# power_12V.net
KiCad netlist of a schematic drawn in Altium Designer
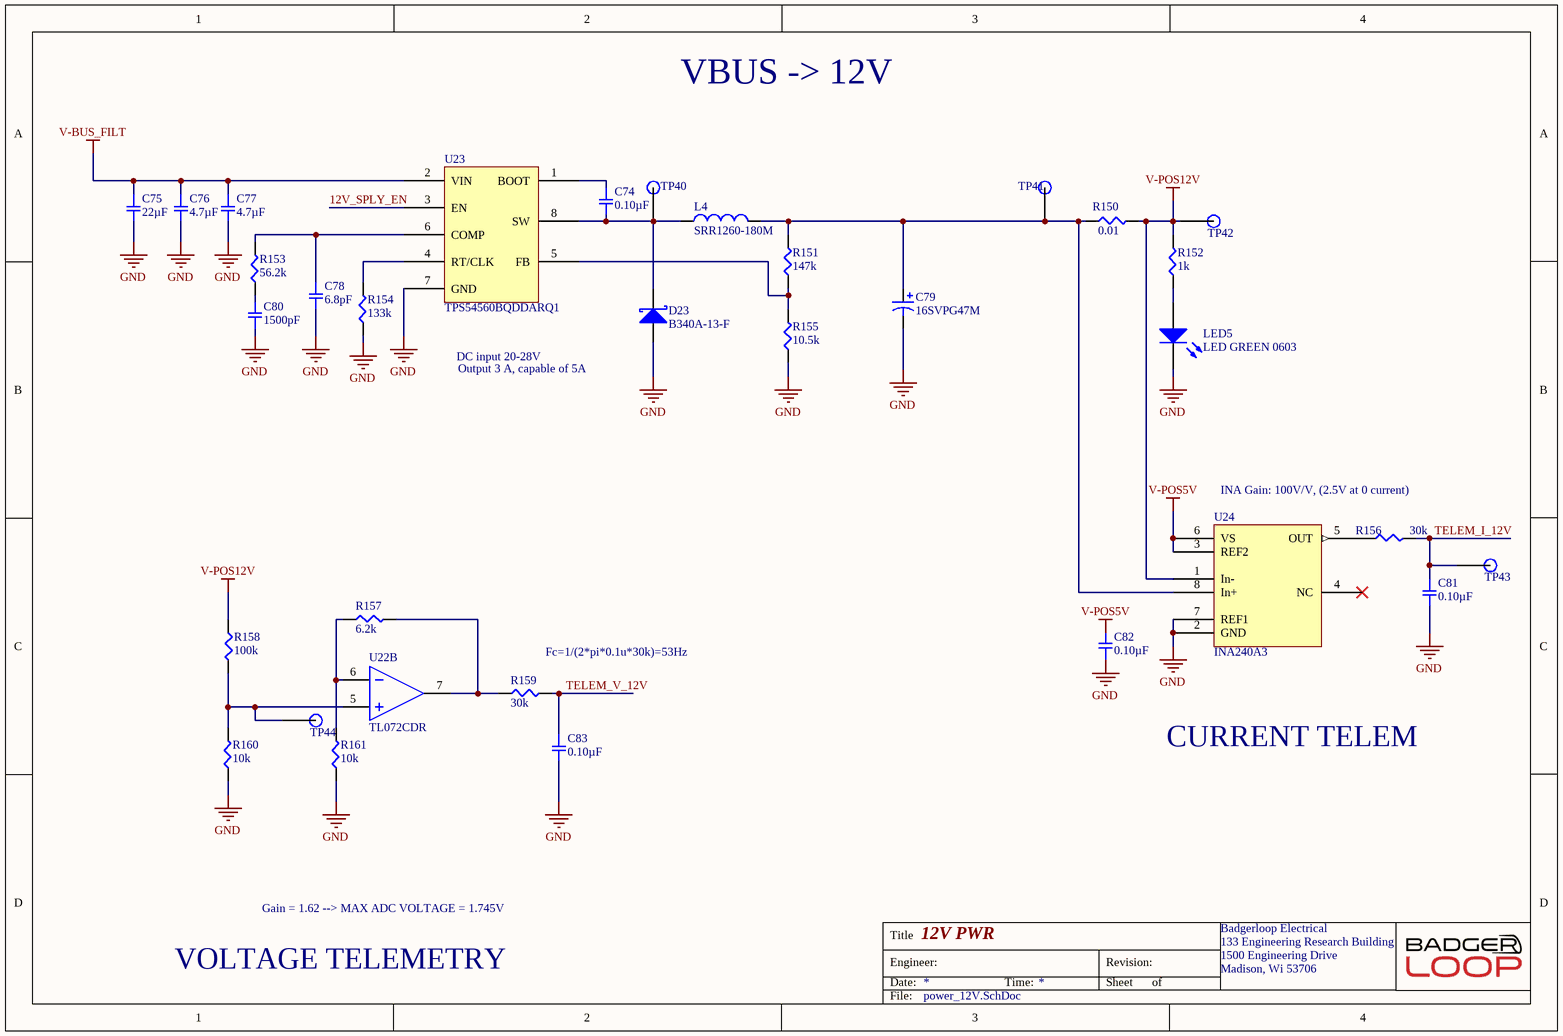
[diagram p0: power_12V.SchDoc]

(export (version "E")
  (design (tool "Eeschema 10.0.6"))
  (components
    (comp (ref "C74")
      (value "0.10µF")
      (footprint "SMD-1206C")
      (description "CAP CER 0.1UF 50V NP0 1206")
      (fields
        (field (name "DIGI-KEY PART NUMBER") "490-8335-1-ND")
        (field (name "PART NUMBER") "GRM31C5C1H104JA01K")
      )
      (libsource (lib "capacitors") (part "GRM31C5C1H104JA01K"))
    )
    (comp (ref "C75")
      (value "22µF")
      (footprint "SMD-1206C")
      (description "CAP CER 22UF 25V X5R 1206")
      (fields
        (field (name "DIGI-KEY PART NUMBER") "490-12451-1-ND")
        (field (name "PART NUMBER") "GRT31CR61E226ME01L")
      )
      (libsource (lib "capacitors") (part "GRT31CR61E226ME01L"))
    )
    (comp (ref "C76")
      (value "4.7µF")
      (footprint "SMD-1206C")
      (description "CAP CER 4.7UF 50V X7S 1206")
      (fields
        (field (name "DIGI-KEY PART NUMBER") "490-11167-1-ND")
        (field (name "PART NUMBER") "GCM31CC71H475KA03L")
      )
      (libsource (lib "capacitors") (part "GCM31CC71H475KA03L"))
    )
    (comp (ref "C77")
      (value "4.7µF")
      (footprint "SMD-1206C")
      (description "CAP CER 4.7UF 50V X7S 1206")
      (fields
        (field (name "DIGI-KEY PART NUMBER") "490-11167-1-ND")
        (field (name "PART NUMBER") "GCM31CC71H475KA03L")
      )
      (libsource (lib "capacitors") (part "GCM31CC71H475KA03L"))
    )
    (comp (ref "C78")
      (value "6.8pF")
      (footprint "SMD-0805C")
      (description "CAP CER 6.8PF 100V NP0 0805")
      (fields
        (field (name "DIGI-KEY PART NUMBER") "490-3596-1-ND")
        (field (name "PART NUMBER") "GQM2195C2A6R8CB01D")
      )
      (libsource (lib "capacitors") (part "GQM2195C2A6R8CB01D"))
    )
    (comp (ref "C79")
      (value "16SVPG47M")
      (footprint "CAPAE110103X126M")
      (fields (field (name "MANUFACTURER") "Panasonic") (field (name "TOLERANCE") "20%"))
      (libsource (lib "capacitors") (part "16SVPG47M"))
    )
    (comp (ref "C80")
      (value "1500pF")
      (footprint "SMD-0805C")
      (description "CAP CER 1500PF 50V NP0 0805")
      (fields
        (field (name "DIGI-KEY PART NUMBER") "490-7772-1-ND")
        (field (name "PART NUMBER") "GRM2165C1H152FA01D")
      )
      (libsource (lib "capacitors") (part "GRM2165C1H152FA01D"))
    )
    (comp (ref "C81")
      (value "0.10µF")
      (footprint "SMD-0805C")
      (description "CAP CER 0.1UF 16V X7R 0805")
      (fields
        (field (name "DIGI-KEY PART NUMBER") "490-1683-1-ND")
        (field (name "PART NUMBER") "GRM219R71C104KA01D")
      )
      (libsource (lib "capacitors") (part "GRM219R71C104KA01D"))
    )
    (comp (ref "C82")
      (value "0.10µF")
      (footprint "SMD-0805C")
      (description "CAP CER 0.1UF 10V U2J 0805")
      (fields
        (field (name "DIGI-KEY PART NUMBER") "490-11592-1-ND")
        (field (name "PART NUMBER") "GRM21B7U1A104JA01L")
      )
      (libsource (lib "capacitors") (part "GRM21B7U1A104JA01L"))
    )
    (comp (ref "C83")
      (value "0.10µF")
      (footprint "SMD-0805C")
      (description "CAP CER 0.1UF 16V X7R 0805")
      (fields
        (field (name "DIGI-KEY PART NUMBER") "490-1683-1-ND")
        (field (name "PART NUMBER") "GRM219R71C104KA01D")
      )
      (libsource (lib "capacitors") (part "GRM219R71C104KA01D"))
    )
    (comp (ref "D23")
      (value "B340A-13-F")
      (footprint "DIOM4326X20N")
      (description "DIODE SCHOTTKY 40V 3A SMA")
      (fields (field (name "MANUFACTURER") "Diodes") (field (name "VOLTAGE") "40V"))
      (libsource (lib "misc") (part "B340A-13-F"))
    )
    (comp (ref "L4")
      (value "SRR1260-180M")
      (footprint "INDM125125X60N")
      (fields (field (name "MANUFACTURER") "Bourns") (field (name "TOLERANCE") "20%"))
      (libsource (lib "inductor") (part "SRR1260-180M"))
    )
    (comp (ref "LED5")
      (value "LED GREEN 0603")
      (footprint "LED 0603 GREEN")
      (fields (field (name "MANUFACTURER") "Lite-On Inc."))
      (libsource (lib "misc") (part "LED GREEN 0603"))
    )
    (comp (ref "R150")
      (value "0.01")
      (footprint "SMD-1206-RES")
      (description "RES SMD 0.01 OHM 1% 1/2W 1206")
      (fields
        (field (name "PART NUMBER") "ERJ-MP2KF10MU")
        (field (name "DIGI-KEY PART NUMBER") "P19322CT-ND")
      )
      (libsource (lib "resistors") (part "ERJ-MP2KF10MU"))
    )
    (comp (ref "R151")
      (value "147k")
      (footprint "SMD-0805-RES")
      (description "RES SMD 147K OHM 1% 1/8W 0805")
      (fields
        (field (name "PART NUMBER") "ERJ-6ENF1473V")
        (field (name "DIGI-KEY PART NUMBER") "P147KCCT-ND")
      )
      (libsource (lib "resistors") (part "ERJ-6ENF1473V"))
    )
    (comp (ref "R152")
      (value "1k")
      (footprint "SMD-0805-RES")
      (description "RES SMD 1K OHM 5% 1/2W 0805")
      (fields
        (field (name "PART NUMBER") "ERJ-P06J102V")
        (field (name "DIGI-KEY PART NUMBER") "P1.0KADCT-ND")
      )
      (libsource (lib "resistors") (part "ERJ-P06J102V"))
    )
    (comp (ref "R153")
      (value "56.2k")
      (footprint "SMD-1206-RES")
      (description "RES SMD 56.2K OHM 1% 1/4W 1206")
      (fields
        (field (name "PART NUMBER") "ERJ-8ENF5622V")
        (field (name "DIGI-KEY PART NUMBER") "P56.2KFCT-ND")
      )
      (libsource (lib "resistors") (part "ERJ-8ENF5622V"))
    )
    (comp (ref "R154")
      (value "133k")
      (footprint "SMD-1206-RES")
      (description "RES SMD 133K OHM 1% 1/4W 1206")
      (fields
        (field (name "PART NUMBER") "ERJ-8ENF1333V")
        (field (name "DIGI-KEY PART NUMBER") "P133KFCT-ND")
      )
      (libsource (lib "resistors") (part "ERJ-8ENF1333V"))
    )
    (comp (ref "R155")
      (value "10.5k")
      (footprint "SMD-1206-RES")
      (description "RES SMD 10.5K OHM 1% 1/4W 1206")
      (fields
        (field (name "PART NUMBER") "ERJ-8ENF1052V")
        (field (name "DIGI-KEY PART NUMBER") "P10.5KFCT-ND")
      )
      (libsource (lib "resistors") (part "ERJ-8ENF1052V"))
    )
    (comp (ref "R156")
      (value "30k")
      (footprint "SMD-0805-RES")
      (description "RES SMD 30K OHM 1% 1/8W 0805")
      (fields
        (field (name "PART NUMBER") "ERJ-6ENF3002V")
        (field (name "DIGI-KEY PART NUMBER") "P30.0KCCT-ND")
      )
      (libsource (lib "resistors") (part "ERJ-6ENF3002V"))
    )
    (comp (ref "R157")
      (value "6.2k")
      (footprint "SMD-0805-RES")
      (description "RES SMD 6.2K OHM 5% 1/2W 0805")
      (fields
        (field (name "PART NUMBER") "ERJ-P06J622V")
        (field (name "DIGI-KEY PART NUMBER") "P6.2KADCT-ND")
      )
      (libsource (lib "resistors") (part "ERJ-P06J622V"))
    )
    (comp (ref "R158")
      (value "100k")
      (footprint "SMD-0805-RES")
      (description "RES SMD 100K OHM 5% 1/2W 0805")
      (fields
        (field (name "PART NUMBER") "ERJ-P06J104V")
        (field (name "DIGI-KEY PART NUMBER") "P100KADCT-ND")
      )
      (libsource (lib "resistors") (part "ERJ-P06J104V"))
    )
    (comp (ref "R159")
      (value "30k")
      (footprint "SMD-0805-RES")
      (description "RES SMD 30K OHM 5% 1/2W 0805")
      (fields (field (name "PART NUMBER") "ERJ-P06J303V") (field (name "DIGI-KEY PART NUMBER") "P30KADCT-ND"))
      (libsource (lib "resistors") (part "ERJ-P06J303V"))
    )
    (comp (ref "R160")
      (value "10k")
      (footprint "SMD-0805-RES")
      (description "RES SMD 10K OHM 5% 1/2W 0805")
      (fields (field (name "PART NUMBER") "ERJ-P06J103V") (field (name "DIGI-KEY PART NUMBER") "P10KADCT-ND"))
      (libsource (lib "resistors") (part "ERJ-P06J103V"))
    )
    (comp (ref "R161")
      (value "10k")
      (footprint "SMD-0805-RES")
      (description "RES SMD 10K OHM 5% 1/2W 0805")
      (fields (field (name "PART NUMBER") "ERJ-P06J103V") (field (name "DIGI-KEY PART NUMBER") "P10KADCT-ND"))
      (libsource (lib "resistors") (part "ERJ-P06J103V"))
    )
    (comp (ref "TP40")
      (value "TP")
      (footprint "Test Point")
      (description "SMD TEST POINT")
      (libsource (lib "misc") (part "TP"))
    )
    (comp (ref "TP41")
      (value "TP")
      (footprint "Test Point")
      (description "SMD TEST POINT")
      (libsource (lib "misc") (part "TP"))
    )
    (comp (ref "TP42")
      (value "TP")
      (footprint "Test Point")
      (description "SMD TEST POINT")
      (libsource (lib "misc") (part "TP"))
    )
    (comp (ref "TP43")
      (value "TP")
      (footprint "Test Point")
      (description "SMD TEST POINT")
      (libsource (lib "misc") (part "TP"))
    )
    (comp (ref "TP44")
      (value "TP")
      (footprint "Test Point")
      (description "SMD TEST POINT")
      (libsource (lib "misc") (part "TP"))
    )
    (comp (ref "U22")
      (value "TL072CDR")
      (footprint "SOP127P600X175-8N")
      (description "IC OPAMP JFET 3MHZ 8SOIC")
      (fields (field (name "MANUFACTURER") "Texas Instruments"))
      (libsource (lib "ic") (part "TL072CDR"))
    )
    (comp (ref "U23")
      (value "TPS54560BQDDARQ1")
      (footprint "SOP127P600X175-8N - Thermal Pad")
      (description "IC REG BUCK SPLT ADJ 5A 8PWRSOIC")
      (fields (field (name "MANUFACTURER") "Texas Instruments"))
      (libsource (lib "ic") (part "TPS54560BQDDARQ1"))
    )
    (comp (ref "U24")
      (value "INA240A3")
      (footprint "SOIC127P600X175-8N")
      (description "IC AMP CURRENT SENSE 8-TSSOP 100V/V")
      (fields (field (name "MANUFACTURER") "Texas Instruments"))
      (libsource (lib "ic") (part "INA240A3"))
    )
  )
  (nets
    (net (code "1") (name "/12V_SPLY_EN") (class "Default")
      (node (ref "U23") (pin "3") (pinfunction "EN_3") (pintype "passive"))
    )
    (net (code "2") (name "/TELEM_I_12V") (class "Default")
      (node (ref "C81") (pin "1") (pinfunction "1_1") (pintype "passive"))
      (node (ref "R156") (pin "2") (pinfunction "2_2") (pintype "passive"))
      (node (ref "TP43") (pin "1") (pinfunction "1_1") (pintype "passive"))
    )
    (net (code "3") (name "/TELEM_V_12V") (class "Default")
      (node (ref "C83") (pin "1") (pinfunction "1_1") (pintype "passive"))
      (node (ref "R159") (pin "2") (pinfunction "2_2") (pintype "passive"))
    )
    (net (code "4") (name "GND") (class "Default")
      (node (ref "C75") (pin "2") (pinfunction "2_2") (pintype "passive"))
      (node (ref "C76") (pin "2") (pinfunction "2_2") (pintype "passive"))
      (node (ref "C77") (pin "2") (pinfunction "2_2") (pintype "passive"))
      (node (ref "C78") (pin "2") (pinfunction "2_2") (pintype "passive"))
      (node (ref "C79") (pin "2") (pinfunction "2_2") (pintype "passive"))
      (node (ref "C80") (pin "1") (pinfunction "1_1") (pintype "passive"))
      (node (ref "C81") (pin "2") (pinfunction "2_2") (pintype "passive"))
      (node (ref "C82") (pin "1") (pinfunction "1_1") (pintype "passive"))
      (node (ref "C83") (pin "2") (pinfunction "2_2") (pintype "passive"))
      (node (ref "D23") (pin "1") (pinfunction "A_1") (pintype "passive"))
      (node (ref "LED5") (pin "2") (pinfunction "K_2") (pintype "passive"))
      (node (ref "R154") (pin "1") (pinfunction "1_1") (pintype "passive"))
      (node (ref "R155") (pin "1") (pinfunction "1_1") (pintype "passive"))
      (node (ref "R160") (pin "1") (pinfunction "1_1") (pintype "passive"))
      (node (ref "R161") (pin "1") (pinfunction "1_1") (pintype "passive"))
      (node (ref "U23") (pin "7") (pinfunction "GND_7") (pintype "passive"))
      (node (ref "U24") (pin "2") (pinfunction "GND_2") (pintype "power_in"))
      (node (ref "U24") (pin "7") (pinfunction "REF1_7") (pintype "passive"))
    )
    (net (code "5") (name "Net-(C80-Pad2)") (class "Default")
      (node (ref "C80") (pin "2") (pinfunction "2_2") (pintype "passive"))
      (node (ref "R153") (pin "1") (pinfunction "1_1") (pintype "passive"))
    )
    (net (code "6") (name "Net-(D23-K)") (class "Default")
      (node (ref "C74") (pin "2") (pinfunction "2_2") (pintype "passive"))
      (node (ref "D23") (pin "2") (pinfunction "K_2") (pintype "passive"))
      (node (ref "L4") (pin "1") (pinfunction "1_1") (pintype "passive"))
      (node (ref "TP40") (pin "1") (pinfunction "1_1") (pintype "passive"))
      (node (ref "U23") (pin "8") (pinfunction "SW_8") (pintype "passive"))
    )
    (net (code "7") (name "Net-(LED5-A)") (class "Default")
      (node (ref "LED5") (pin "1") (pinfunction "A_1") (pintype "passive"))
      (node (ref "R152") (pin "1") (pinfunction "1_1") (pintype "passive"))
    )
    (net (code "8") (name "Net-(U22B-IN+)") (class "Default")
      (node (ref "R158") (pin "2") (pinfunction "2_2") (pintype "passive"))
      (node (ref "R160") (pin "2") (pinfunction "2_2") (pintype "passive"))
      (node (ref "TP44") (pin "1") (pinfunction "1_1") (pintype "passive"))
      (node (ref "U22") (pin "5") (pinfunction "IN+_5") (pintype "passive"))
    )
    (net (code "9") (name "Net-(U22B-IN-)") (class "Default")
      (node (ref "R157") (pin "1") (pinfunction "1_1") (pintype "passive"))
      (node (ref "R161") (pin "2") (pinfunction "2_2") (pintype "passive"))
      (node (ref "U22") (pin "6") (pinfunction "IN-_6") (pintype "passive"))
    )
    (net (code "10") (name "Net-(U22B-OUT)") (class "Default")
      (node (ref "R157") (pin "2") (pinfunction "2_2") (pintype "passive"))
      (node (ref "R159") (pin "1") (pinfunction "1_1") (pintype "passive"))
      (node (ref "U22") (pin "7") (pinfunction "OUT_7") (pintype "passive"))
    )
    (net (code "11") (name "Net-(U23-BOOT)") (class "Default")
      (node (ref "C74") (pin "1") (pinfunction "1_1") (pintype "passive"))
      (node (ref "U23") (pin "1") (pinfunction "BOOT_1") (pintype "passive"))
    )
    (net (code "12") (name "Net-(U23-COMP)") (class "Default")
      (node (ref "C78") (pin "1") (pinfunction "1_1") (pintype "passive"))
      (node (ref "R153") (pin "2") (pinfunction "2_2") (pintype "passive"))
      (node (ref "U23") (pin "6") (pinfunction "COMP_6") (pintype "passive"))
    )
    (net (code "13") (name "Net-(U23-FB)") (class "Default")
      (node (ref "R151") (pin "1") (pinfunction "1_1") (pintype "passive"))
      (node (ref "R155") (pin "2") (pinfunction "2_2") (pintype "passive"))
      (node (ref "U23") (pin "5") (pinfunction "FB_5") (pintype "passive"))
    )
    (net (code "14") (name "Net-(U23-RT{slash}CLK)") (class "Default")
      (node (ref "R154") (pin "2") (pinfunction "2_2") (pintype "passive"))
      (node (ref "U23") (pin "4") (pinfunction "RT/CLK_4") (pintype "passive"))
    )
    (net (code "15") (name "Net-(U24-In+)") (class "Default")
      (node (ref "C79") (pin "1") (pinfunction "1_1") (pintype "passive"))
      (node (ref "L4") (pin "2") (pinfunction "2_2") (pintype "passive"))
      (node (ref "R150") (pin "1") (pinfunction "1_1") (pintype "passive"))
      (node (ref "R151") (pin "2") (pinfunction "2_2") (pintype "passive"))
      (node (ref "TP41") (pin "1") (pinfunction "1_1") (pintype "passive"))
      (node (ref "U24") (pin "8") (pinfunction "In+_8") (pintype "passive"))
    )
    (net (code "16") (name "Net-(U24-OUT)") (class "Default")
      (node (ref "R156") (pin "1") (pinfunction "1_1") (pintype "passive"))
      (node (ref "U24") (pin "5") (pinfunction "OUT_5") (pintype "output"))
    )
    (net (code "17") (name "V-BUS_FILT") (class "Default")
      (node (ref "C75") (pin "1") (pinfunction "1_1") (pintype "passive"))
      (node (ref "C76") (pin "1") (pinfunction "1_1") (pintype "passive"))
      (node (ref "C77") (pin "1") (pinfunction "1_1") (pintype "passive"))
      (node (ref "U23") (pin "2") (pinfunction "VIN_2") (pintype "passive"))
    )
    (net (code "18") (name "V-POS5V") (class "Default")
      (node (ref "C82") (pin "2") (pinfunction "2_2") (pintype "passive"))
      (node (ref "U24") (pin "3") (pinfunction "REF2_3") (pintype "passive"))
      (node (ref "U24") (pin "6") (pinfunction "VS_6") (pintype "power_in"))
    )
    (net (code "19") (name "V-POS12V") (class "Default")
      (node (ref "R150") (pin "2") (pinfunction "2_2") (pintype "passive"))
      (node (ref "R152") (pin "2") (pinfunction "2_2") (pintype "passive"))
      (node (ref "R158") (pin "1") (pinfunction "1_1") (pintype "passive"))
      (node (ref "TP42") (pin "1") (pinfunction "1_1") (pintype "passive"))
      (node (ref "U24") (pin "1") (pinfunction "In-_1") (pintype "passive"))
    )
    (net (code "20") (name "unconnected-(U24-NC-Pad4)") (class "Default")
      (node (ref "U24") (pin "4") (pinfunction "NC_4") (pintype "passive+no_connect"))
    )
  )
)
